# fablab_example_board_v2.net
KiCad netlist of a schematic drawn in EAGLE
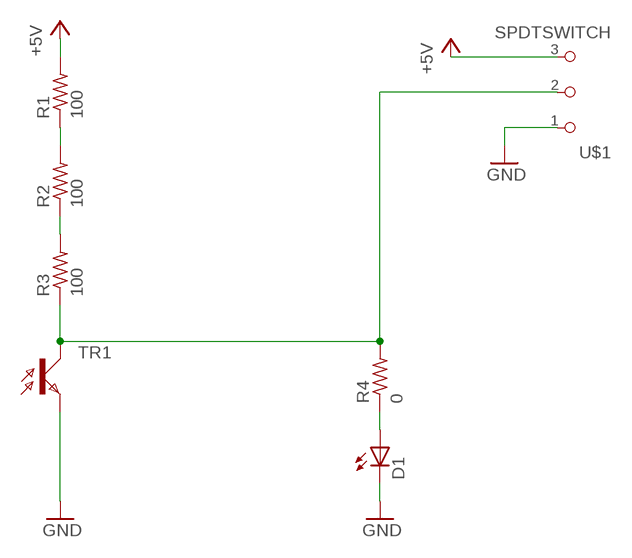
[diagram p0: schematic, sheet 1]

(export (version "E")
  (design (tool "Eeschema 10.0.6"))
  (components
    (comp (ref "D1")
      (value "LEDFAB1206")
      (footprint "eagle-import:LED1206FAB")
      (libsource (lib "eagle-import") (part "LEDFAB1206"))
    )
    (comp (ref "R1")
      (value "100")
      (footprint "eagle-import:R1206FAB")
      (libsource (lib "eagle-import") (part "RES-US1206FAB"))
    )
    (comp (ref "R2")
      (value "100")
      (footprint "eagle-import:R1206FAB")
      (libsource (lib "eagle-import") (part "RES-US1206FAB"))
    )
    (comp (ref "R3")
      (value "100")
      (footprint "eagle-import:R1206FAB")
      (libsource (lib "eagle-import") (part "RES-US1206FAB"))
    )
    (comp (ref "R4")
      (value "0")
      (footprint "eagle-import:R1206FAB")
      (libsource (lib "eagle-import") (part "RES-US1206FAB"))
    )
    (comp (ref "TR1")
      (value "PHOTOTRANSISTOR-NPN1206")
      (footprint "eagle-import:OP1206")
      (libsource (lib "eagle-import") (part "PHOTOTRANSISTOR-NPN1206"))
    )
    (comp (ref "U$1")
      (value "SPDTSWITCH")
      (footprint "eagle-import:SPDTSWITCH")
      (libsource (lib "eagle-import") (part "SPDTSWITCH"))
    )
  )
  (nets
    (net (code "1") (name "+5V") (class "Default")
      (node (ref "R1") (pin "2") (pinfunction "2_2") (pintype "passive"))
      (node (ref "U$1") (pin "3") (pinfunction "3_3") (pintype "passive"))
    )
    (net (code "2") (name "GND") (class "Default")
      (node (ref "D1") (pin "2") (pinfunction "C_2") (pintype "passive"))
      (node (ref "TR1") (pin "E") (pinfunction "E_E") (pintype "passive"))
      (node (ref "U$1") (pin "1") (pinfunction "1_1") (pintype "passive"))
    )
    (net (code "3") (name "Net-(D1-A)") (class "Default")
      (node (ref "D1") (pin "1") (pinfunction "A_1") (pintype "passive"))
      (node (ref "R4") (pin "1") (pinfunction "1_1") (pintype "passive"))
    )
    (net (code "4") (name "Net-(R1-Pad1)") (class "Default")
      (node (ref "R1") (pin "1") (pinfunction "1_1") (pintype "passive"))
      (node (ref "R2") (pin "2") (pinfunction "2_2") (pintype "passive"))
    )
    (net (code "5") (name "Net-(R2-Pad1)") (class "Default")
      (node (ref "R2") (pin "1") (pinfunction "1_1") (pintype "passive"))
      (node (ref "R3") (pin "2") (pinfunction "2_2") (pintype "passive"))
    )
    (net (code "6") (name "Net-(R3-Pad1)") (class "Default")
      (node (ref "R3") (pin "1") (pinfunction "1_1") (pintype "passive"))
      (node (ref "R4") (pin "2") (pinfunction "2_2") (pintype "passive"))
      (node (ref "TR1") (pin "C") (pinfunction "C_C") (pintype "passive"))
      (node (ref "U$1") (pin "2") (pinfunction "2_2") (pintype "passive"))
    )
  )
)
